# pcb_univ_3-1-0-x-rev2.net
KiCad netlist of a schematic drawn in EAGLE
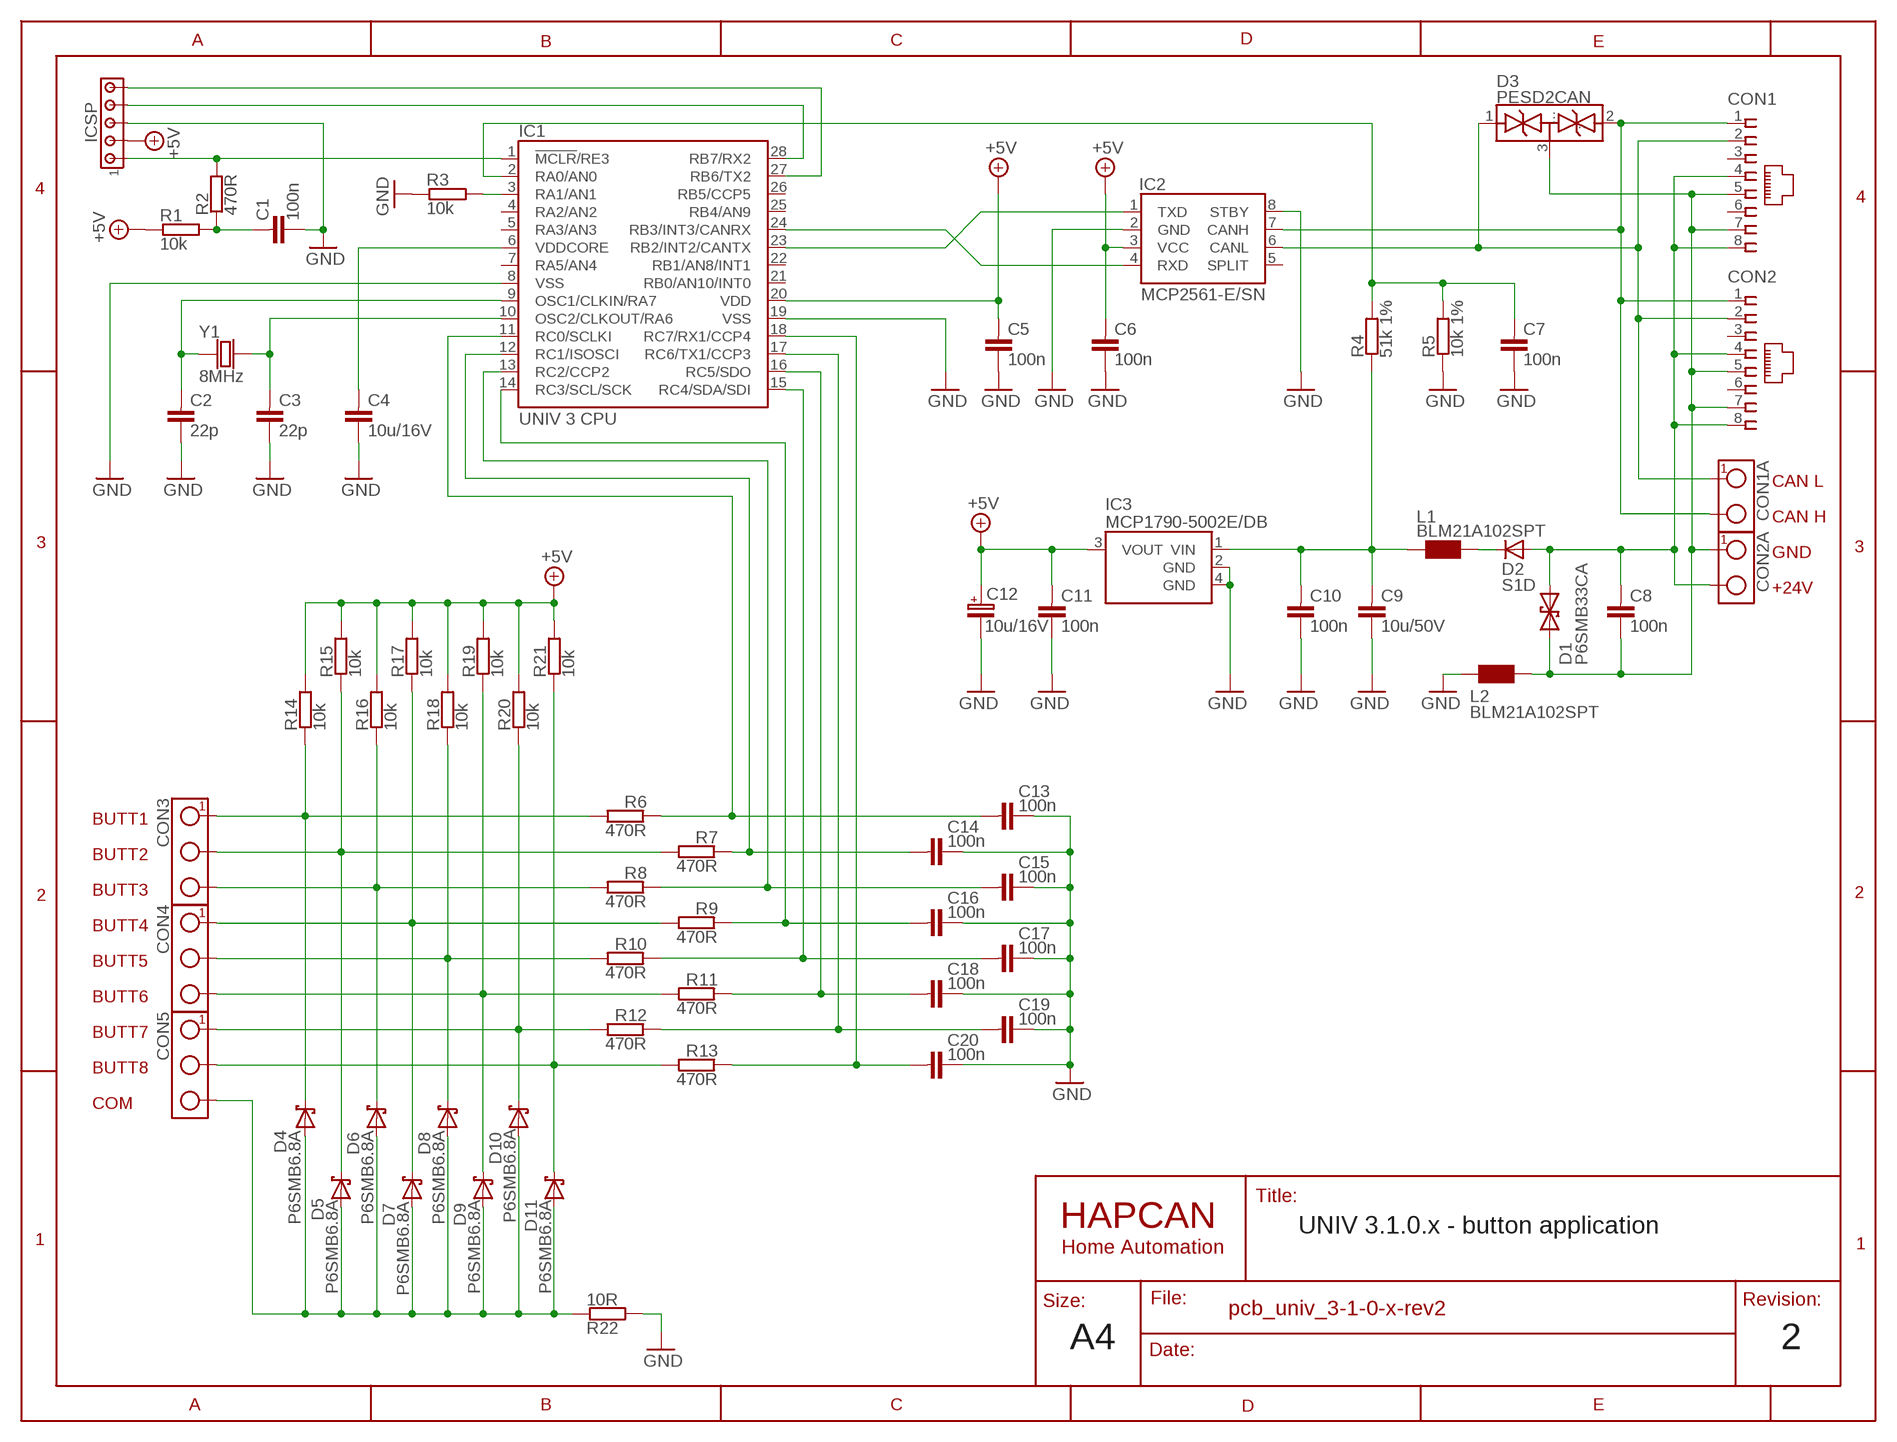
[diagram p0: schematic, sheet 1]

(export (version "E")
  (design (tool "Eeschema 10.0.6"))
  (components
    (comp (ref "C1")
      (value "100n")
      (footprint "eagle-import:0805")
      (libsource (lib "eagle-import") (part "CAPACITOR0805"))
    )
    (comp (ref "C2")
      (value "22p")
      (footprint "eagle-import:0805")
      (libsource (lib "eagle-import") (part "CAPACITOR0805"))
    )
    (comp (ref "C3")
      (value "22p")
      (footprint "eagle-import:0805")
      (libsource (lib "eagle-import") (part "CAPACITOR0805"))
    )
    (comp (ref "C4")
      (value "10u/16V")
      (footprint "eagle-import:0805")
      (libsource (lib "eagle-import") (part "CAPACITOR0805"))
    )
    (comp (ref "C5")
      (value "100n")
      (footprint "eagle-import:0805")
      (libsource (lib "eagle-import") (part "CAPACITOR0805"))
    )
    (comp (ref "C6")
      (value "100n")
      (footprint "eagle-import:0805")
      (libsource (lib "eagle-import") (part "CAPACITOR0805"))
    )
    (comp (ref "C7")
      (value "100n")
      (footprint "eagle-import:0805")
      (libsource (lib "eagle-import") (part "CAPACITOR0805"))
    )
    (comp (ref "C8")
      (value "100n")
      (footprint "eagle-import:0805")
      (libsource (lib "eagle-import") (part "CAPACITOR0805"))
    )
    (comp (ref "C9")
      (value "10u/50V")
      (footprint "eagle-import:1210")
      (libsource (lib "eagle-import") (part "CAPACITOR1210"))
    )
    (comp (ref "C10")
      (value "100n")
      (footprint "eagle-import:0805")
      (libsource (lib "eagle-import") (part "CAPACITOR0805"))
    )
    (comp (ref "C11")
      (value "100n")
      (footprint "eagle-import:0805")
      (libsource (lib "eagle-import") (part "CAPACITOR0805"))
    )
    (comp (ref "C12")
      (value "10u/16V")
      (footprint "eagle-import:SMC_B")
      (libsource (lib "eagle-import") (part "CAPACITOR-POLARIZED-SMC_B"))
    )
    (comp (ref "C13")
      (value "100n")
      (footprint "eagle-import:0805")
      (libsource (lib "eagle-import") (part "CAPACITOR0805"))
    )
    (comp (ref "C14")
      (value "100n")
      (footprint "eagle-import:0805")
      (libsource (lib "eagle-import") (part "CAPACITOR0805"))
    )
    (comp (ref "C15")
      (value "100n")
      (footprint "eagle-import:0805")
      (libsource (lib "eagle-import") (part "CAPACITOR0805"))
    )
    (comp (ref "C16")
      (value "100n")
      (footprint "eagle-import:0805")
      (libsource (lib "eagle-import") (part "CAPACITOR0805"))
    )
    (comp (ref "C17")
      (value "100n")
      (footprint "eagle-import:0805")
      (libsource (lib "eagle-import") (part "CAPACITOR0805"))
    )
    (comp (ref "C18")
      (value "100n")
      (footprint "eagle-import:0805")
      (libsource (lib "eagle-import") (part "CAPACITOR0805"))
    )
    (comp (ref "C19")
      (value "100n")
      (footprint "eagle-import:0805")
      (libsource (lib "eagle-import") (part "CAPACITOR0805"))
    )
    (comp (ref "C20")
      (value "100n")
      (footprint "eagle-import:0805")
      (libsource (lib "eagle-import") (part "CAPACITOR0805"))
    )
    (comp (ref "CON1")
      (value "RJ45-SOCKET")
      (footprint "eagle-import:RJ45-PCB-SOCKET")
      (libsource (lib "eagle-import") (part "RJ45-SOCKET"))
    )
    (comp (ref "CON1A")
      (value "TERMINAL-2")
      (footprint "eagle-import:ARK2-5X10,5MM")
      (libsource (lib "eagle-import") (part "TERMINAL-2-5X10,5MM"))
    )
    (comp (ref "CON2")
      (value "RJ45-SOCKET")
      (footprint "eagle-import:RJ45-PCB-SOCKET")
      (libsource (lib "eagle-import") (part "RJ45-SOCKET"))
    )
    (comp (ref "CON2A")
      (value "TERMINAL-2")
      (footprint "eagle-import:ARK2-5X10,5MM")
      (libsource (lib "eagle-import") (part "TERMINAL-2-5X10,5MM"))
    )
    (comp (ref "CON3")
      (value "TERMINAL-3")
      (footprint "eagle-import:ARK3-5X10.5MM")
      (libsource (lib "eagle-import") (part "TERMINAL-3-5X10.5MM"))
    )
    (comp (ref "CON4")
      (value "TERMINAL-3")
      (footprint "eagle-import:ARK3-5X10.5MM")
      (libsource (lib "eagle-import") (part "TERMINAL-3-5X10.5MM"))
    )
    (comp (ref "CON5")
      (value "TERMINAL-3")
      (footprint "eagle-import:ARK3-5X10.5MM")
      (libsource (lib "eagle-import") (part "TERMINAL-3-5X10.5MM"))
    )
    (comp (ref "D1")
      (value "P6SMB33CA")
      (footprint "eagle-import:DO-214_TRANSIL2")
      (libsource (lib "eagle-import") (part "DIODE_TRANSIL2"))
    )
    (comp (ref "D2")
      (value "S1D")
      (footprint "eagle-import:DO-214")
      (libsource (lib "eagle-import") (part "DIODE_DO-214"))
    )
    (comp (ref "D3")
      (value "PESD2CAN")
      (footprint "eagle-import:SOT-23")
      (libsource (lib "eagle-import") (part "PESD2CANSOT-23"))
    )
    (comp (ref "D4")
      (value "P6SMB6.8A")
      (footprint "eagle-import:DO-214")
      (libsource (lib "eagle-import") (part "DIODE_TRANSIL1_DO214"))
    )
    (comp (ref "D5")
      (value "P6SMB6.8A")
      (footprint "eagle-import:DO-214")
      (libsource (lib "eagle-import") (part "DIODE_TRANSIL1_DO214"))
    )
    (comp (ref "D6")
      (value "P6SMB6.8A")
      (footprint "eagle-import:DO-214")
      (libsource (lib "eagle-import") (part "DIODE_TRANSIL1_DO214"))
    )
    (comp (ref "D7")
      (value "P6SMB6.8A")
      (footprint "eagle-import:DO-214")
      (libsource (lib "eagle-import") (part "DIODE_TRANSIL1_DO214"))
    )
    (comp (ref "D8")
      (value "P6SMB6.8A")
      (footprint "eagle-import:DO-214")
      (libsource (lib "eagle-import") (part "DIODE_TRANSIL1_DO214"))
    )
    (comp (ref "D9")
      (value "P6SMB6.8A")
      (footprint "eagle-import:DO-214")
      (libsource (lib "eagle-import") (part "DIODE_TRANSIL1_DO214"))
    )
    (comp (ref "D10")
      (value "P6SMB6.8A")
      (footprint "eagle-import:DO-214")
      (libsource (lib "eagle-import") (part "DIODE_TRANSIL1_DO214"))
    )
    (comp (ref "D11")
      (value "P6SMB6.8A")
      (footprint "eagle-import:DO-214")
      (libsource (lib "eagle-import") (part "DIODE_TRANSIL1_DO214"))
    )
    (comp (ref "IC1")
      (value "UNIV 3 CPU")
      (footprint "eagle-import:UNIV3CPU")
      (libsource (lib "eagle-import") (part "UNIV3CPU-I/SO"))
    )
    (comp (ref "IC2")
      (value "MCP2561-E/SN")
      (footprint "eagle-import:SO-08")
      (libsource (lib "eagle-import") (part "MCP2561-E/SN"))
    )
    (comp (ref "IC3")
      (value "MCP1790-5002E/DB")
      (footprint "eagle-import:SOT-223")
      (libsource (lib "eagle-import") (part "MCP1790"))
    )
    (comp (ref "ICSP")
      (value "HEADER5")
      (footprint "eagle-import:SIP-5")
      (libsource (lib "eagle-import") (part "HEADER5"))
    )
    (comp (ref "L1")
      (value "BLM21A102SPT")
      (footprint "eagle-import:0805")
      (libsource (lib "eagle-import") (part "CHOKE0805"))
    )
    (comp (ref "L2")
      (value "BLM21A102SPT")
      (footprint "eagle-import:0805")
      (libsource (lib "eagle-import") (part "CHOKE0805"))
    )
    (comp (ref "R1")
      (value "10k")
      (footprint "eagle-import:0805")
      (libsource (lib "eagle-import") (part "RESISTOR0805"))
    )
    (comp (ref "R2")
      (value "470R")
      (footprint "eagle-import:0805")
      (libsource (lib "eagle-import") (part "RESISTOR0805"))
    )
    (comp (ref "R3")
      (value "10k")
      (footprint "eagle-import:0805")
      (libsource (lib "eagle-import") (part "RESISTOR0805"))
    )
    (comp (ref "R4")
      (value "51k 1%")
      (footprint "eagle-import:0805")
      (libsource (lib "eagle-import") (part "RESISTOR0805"))
    )
    (comp (ref "R5")
      (value "10k 1%")
      (footprint "eagle-import:0805")
      (libsource (lib "eagle-import") (part "RESISTOR0805"))
    )
    (comp (ref "R6")
      (value "470R")
      (footprint "eagle-import:0805")
      (libsource (lib "eagle-import") (part "RESISTOR0805"))
    )
    (comp (ref "R7")
      (value "470R")
      (footprint "eagle-import:0805")
      (libsource (lib "eagle-import") (part "RESISTOR0805"))
    )
    (comp (ref "R8")
      (value "470R")
      (footprint "eagle-import:0805")
      (libsource (lib "eagle-import") (part "RESISTOR0805"))
    )
    (comp (ref "R9")
      (value "470R")
      (footprint "eagle-import:0805")
      (libsource (lib "eagle-import") (part "RESISTOR0805"))
    )
    (comp (ref "R10")
      (value "470R")
      (footprint "eagle-import:0805")
      (libsource (lib "eagle-import") (part "RESISTOR0805"))
    )
    (comp (ref "R11")
      (value "470R")
      (footprint "eagle-import:0805")
      (libsource (lib "eagle-import") (part "RESISTOR0805"))
    )
    (comp (ref "R12")
      (value "470R")
      (footprint "eagle-import:0805")
      (libsource (lib "eagle-import") (part "RESISTOR0805"))
    )
    (comp (ref "R13")
      (value "470R")
      (footprint "eagle-import:0805")
      (libsource (lib "eagle-import") (part "RESISTOR0805"))
    )
    (comp (ref "R14")
      (value "10k")
      (footprint "eagle-import:0805")
      (libsource (lib "eagle-import") (part "RESISTOR0805"))
    )
    (comp (ref "R15")
      (value "10k")
      (footprint "eagle-import:0805")
      (libsource (lib "eagle-import") (part "RESISTOR0805"))
    )
    (comp (ref "R16")
      (value "10k")
      (footprint "eagle-import:0805")
      (libsource (lib "eagle-import") (part "RESISTOR0805"))
    )
    (comp (ref "R17")
      (value "10k")
      (footprint "eagle-import:0805")
      (libsource (lib "eagle-import") (part "RESISTOR0805"))
    )
    (comp (ref "R18")
      (value "10k")
      (footprint "eagle-import:0805")
      (libsource (lib "eagle-import") (part "RESISTOR0805"))
    )
    (comp (ref "R19")
      (value "10k")
      (footprint "eagle-import:0805")
      (libsource (lib "eagle-import") (part "RESISTOR0805"))
    )
    (comp (ref "R20")
      (value "10k")
      (footprint "eagle-import:0805")
      (libsource (lib "eagle-import") (part "RESISTOR0805"))
    )
    (comp (ref "R21")
      (value "10k")
      (footprint "eagle-import:0805")
      (libsource (lib "eagle-import") (part "RESISTOR0805"))
    )
    (comp (ref "R22")
      (value "10R")
      (footprint "eagle-import:0805")
      (libsource (lib "eagle-import") (part "RESISTOR0805"))
    )
    (comp (ref "Y1")
      (value "8MHz")
      (footprint "eagle-import:CRYSTAL-HC49V")
      (libsource (lib "eagle-import") (part "CRYSTAL-HC49V"))
    )
  )
  (nets
    (net (code "1") (name "+5V") (class "Default")
      (node (ref "C11") (pin "1") (pinfunction "1_1") (pintype "passive"))
      (node (ref "C12") (pin "+") (pinfunction "1_+") (pintype "passive"))
      (node (ref "C5") (pin "1") (pinfunction "1_1") (pintype "passive"))
      (node (ref "C6") (pin "1") (pinfunction "1_1") (pintype "passive"))
      (node (ref "IC1") (pin "20") (pinfunction "VDD_20") (pintype "bidirectional"))
      (node (ref "IC2") (pin "3") (pinfunction "VCC_3") (pintype "bidirectional"))
      (node (ref "IC3") (pin "3") (pinfunction "VOUT_3") (pintype "bidirectional"))
      (node (ref "ICSP") (pin "2") (pinfunction "2_2") (pintype "passive"))
      (node (ref "R1") (pin "1") (pinfunction "1_1") (pintype "passive"))
      (node (ref "R14") (pin "2") (pinfunction "2_2") (pintype "passive"))
      (node (ref "R15") (pin "2") (pinfunction "2_2") (pintype "passive"))
      (node (ref "R16") (pin "2") (pinfunction "2_2") (pintype "passive"))
      (node (ref "R17") (pin "2") (pinfunction "2_2") (pintype "passive"))
      (node (ref "R18") (pin "2") (pinfunction "2_2") (pintype "passive"))
      (node (ref "R19") (pin "2") (pinfunction "2_2") (pintype "passive"))
      (node (ref "R20") (pin "2") (pinfunction "2_2") (pintype "passive"))
      (node (ref "R21") (pin "2") (pinfunction "2_2") (pintype "passive"))
    )
    (net (code "2") (name "GND") (class "Default")
      (node (ref "C1") (pin "2") (pinfunction "2_2") (pintype "passive"))
      (node (ref "C10") (pin "2") (pinfunction "2_2") (pintype "passive"))
      (node (ref "C11") (pin "2") (pinfunction "2_2") (pintype "passive"))
      (node (ref "C12") (pin "-") (pinfunction "2_-") (pintype "passive"))
      (node (ref "C13") (pin "2") (pinfunction "2_2") (pintype "passive"))
      (node (ref "C14") (pin "2") (pinfunction "2_2") (pintype "passive"))
      (node (ref "C15") (pin "2") (pinfunction "2_2") (pintype "passive"))
      (node (ref "C16") (pin "2") (pinfunction "2_2") (pintype "passive"))
      (node (ref "C17") (pin "2") (pinfunction "2_2") (pintype "passive"))
      (node (ref "C18") (pin "2") (pinfunction "2_2") (pintype "passive"))
      (node (ref "C19") (pin "2") (pinfunction "2_2") (pintype "passive"))
      (node (ref "C2") (pin "2") (pinfunction "2_2") (pintype "passive"))
      (node (ref "C20") (pin "2") (pinfunction "2_2") (pintype "passive"))
      (node (ref "C3") (pin "2") (pinfunction "2_2") (pintype "passive"))
      (node (ref "C4") (pin "2") (pinfunction "2_2") (pintype "passive"))
      (node (ref "C5") (pin "2") (pinfunction "2_2") (pintype "passive"))
      (node (ref "C6") (pin "2") (pinfunction "2_2") (pintype "passive"))
      (node (ref "C7") (pin "2") (pinfunction "2_2") (pintype "passive"))
      (node (ref "C9") (pin "2") (pinfunction "2_2") (pintype "passive"))
      (node (ref "IC1") (pin "19") (pinfunction "VSS_19") (pintype "bidirectional"))
      (node (ref "IC1") (pin "8") (pinfunction "VSS_8") (pintype "bidirectional"))
      (node (ref "IC2") (pin "2") (pinfunction "GND_2") (pintype "bidirectional"))
      (node (ref "IC2") (pin "8") (pinfunction "STBY_8") (pintype "bidirectional"))
      (node (ref "IC3") (pin "2") (pinfunction "GND_2") (pintype "bidirectional"))
      (node (ref "IC3") (pin "4") (pinfunction "GND_4") (pintype "bidirectional"))
      (node (ref "ICSP") (pin "3") (pinfunction "3_3") (pintype "passive"))
      (node (ref "L2") (pin "1") (pinfunction "1_1") (pintype "passive"))
      (node (ref "R22") (pin "2") (pinfunction "2_2") (pintype "passive"))
      (node (ref "R3") (pin "1") (pinfunction "1_1") (pintype "passive"))
      (node (ref "R5") (pin "1") (pinfunction "1_1") (pintype "passive"))
    )
    (net (code "3") (name "Net-(C1-Pad1)") (class "Default")
      (node (ref "C1") (pin "1") (pinfunction "1_1") (pintype "passive"))
      (node (ref "R1") (pin "2") (pinfunction "2_2") (pintype "passive"))
      (node (ref "R2") (pin "1") (pinfunction "1_1") (pintype "passive"))
    )
    (net (code "4") (name "Net-(CON3-Pad1)") (class "Default")
      (node (ref "CON3") (pin "1") (pinfunction "1_1") (pintype "passive"))
      (node (ref "D4") (pin "C") (pinfunction "C_C") (pintype "passive"))
      (node (ref "R14") (pin "1") (pinfunction "1_1") (pintype "passive"))
      (node (ref "R6") (pin "2") (pinfunction "2_2") (pintype "passive"))
    )
    (net (code "5") (name "Net-(CON3-Pad2)") (class "Default")
      (node (ref "CON3") (pin "2") (pinfunction "2_2") (pintype "passive"))
      (node (ref "D5") (pin "C") (pinfunction "C_C") (pintype "passive"))
      (node (ref "R15") (pin "1") (pinfunction "1_1") (pintype "passive"))
      (node (ref "R7") (pin "2") (pinfunction "2_2") (pintype "passive"))
    )
    (net (code "6") (name "Net-(CON3-Pad3)") (class "Default")
      (node (ref "CON3") (pin "3") (pinfunction "3_3") (pintype "passive"))
      (node (ref "D6") (pin "C") (pinfunction "C_C") (pintype "passive"))
      (node (ref "R16") (pin "1") (pinfunction "1_1") (pintype "passive"))
      (node (ref "R8") (pin "2") (pinfunction "2_2") (pintype "passive"))
    )
    (net (code "7") (name "Net-(CON4-Pad1)") (class "Default")
      (node (ref "CON4") (pin "1") (pinfunction "1_1") (pintype "passive"))
      (node (ref "D7") (pin "C") (pinfunction "C_C") (pintype "passive"))
      (node (ref "R17") (pin "1") (pinfunction "1_1") (pintype "passive"))
      (node (ref "R9") (pin "2") (pinfunction "2_2") (pintype "passive"))
    )
    (net (code "8") (name "Net-(CON4-Pad2)") (class "Default")
      (node (ref "CON4") (pin "2") (pinfunction "2_2") (pintype "passive"))
      (node (ref "D8") (pin "C") (pinfunction "C_C") (pintype "passive"))
      (node (ref "R10") (pin "2") (pinfunction "2_2") (pintype "passive"))
      (node (ref "R18") (pin "1") (pinfunction "1_1") (pintype "passive"))
    )
    (net (code "9") (name "Net-(CON4-Pad3)") (class "Default")
      (node (ref "CON4") (pin "3") (pinfunction "3_3") (pintype "passive"))
      (node (ref "D9") (pin "C") (pinfunction "C_C") (pintype "passive"))
      (node (ref "R11") (pin "2") (pinfunction "2_2") (pintype "passive"))
      (node (ref "R19") (pin "1") (pinfunction "1_1") (pintype "passive"))
    )
    (net (code "10") (name "Net-(CON5-Pad1)") (class "Default")
      (node (ref "CON5") (pin "1") (pinfunction "1_1") (pintype "passive"))
      (node (ref "D10") (pin "C") (pinfunction "C_C") (pintype "passive"))
      (node (ref "R12") (pin "2") (pinfunction "2_2") (pintype "passive"))
      (node (ref "R20") (pin "1") (pinfunction "1_1") (pintype "passive"))
    )
    (net (code "11") (name "Net-(CON5-Pad2)") (class "Default")
      (node (ref "CON5") (pin "2") (pinfunction "2_2") (pintype "passive"))
      (node (ref "D11") (pin "C") (pinfunction "C_C") (pintype "passive"))
      (node (ref "R13") (pin "2") (pinfunction "2_2") (pintype "passive"))
      (node (ref "R21") (pin "1") (pinfunction "1_1") (pintype "passive"))
    )
    (net (code "12") (name "Net-(CON5-Pad3)") (class "Default")
      (node (ref "CON5") (pin "3") (pinfunction "3_3") (pintype "passive"))
      (node (ref "D10") (pin "A") (pinfunction "A_A") (pintype "passive"))
      (node (ref "D11") (pin "A") (pinfunction "A_A") (pintype "passive"))
      (node (ref "D4") (pin "A") (pinfunction "A_A") (pintype "passive"))
      (node (ref "D5") (pin "A") (pinfunction "A_A") (pintype "passive"))
      (node (ref "D6") (pin "A") (pinfunction "A_A") (pintype "passive"))
      (node (ref "D7") (pin "A") (pinfunction "A_A") (pintype "passive"))
      (node (ref "D8") (pin "A") (pinfunction "A_A") (pintype "passive"))
      (node (ref "D9") (pin "A") (pinfunction "A_A") (pintype "passive"))
      (node (ref "R22") (pin "1") (pinfunction "1_1") (pintype "passive"))
    )
    (net (code "13") (name "Net-(D1-1)") (class "Default")
      (node (ref "C8") (pin "1") (pinfunction "1_1") (pintype "passive"))
      (node (ref "CON1") (pin "4") (pinfunction "4_4") (pintype "passive"))
      (node (ref "CON1") (pin "8") (pinfunction "8_8") (pintype "passive"))
      (node (ref "CON2") (pin "4") (pinfunction "4_4") (pintype "passive"))
      (node (ref "CON2") (pin "8") (pinfunction "8_8") (pintype "passive"))
      (node (ref "CON2A") (pin "2") (pinfunction "2_2") (pintype "passive"))
      (node (ref "D1") (pin "A") (pinfunction "1_A") (pintype "passive"))
      (node (ref "D2") (pin "A") (pinfunction "A_A") (pintype "passive"))
    )
    (net (code "14") (name "Net-(D1-2)") (class "Default")
      (node (ref "C8") (pin "2") (pinfunction "2_2") (pintype "passive"))
      (node (ref "CON1") (pin "5") (pinfunction "5_5") (pintype "passive"))
      (node (ref "CON1") (pin "7") (pinfunction "7_7") (pintype "passive"))
      (node (ref "CON2") (pin "5") (pinfunction "5_5") (pintype "passive"))
      (node (ref "CON2") (pin "7") (pinfunction "7_7") (pintype "passive"))
      (node (ref "CON2A") (pin "1") (pinfunction "1_1") (pintype "passive"))
      (node (ref "D1") (pin "C") (pinfunction "2_C") (pintype "passive"))
      (node (ref "D3") (pin "3") (pinfunction "..._3") (pintype "bidirectional"))
      (node (ref "L2") (pin "2") (pinfunction "2_2") (pintype "passive"))
    )
    (net (code "15") (name "Net-(D2-PadC)") (class "Default")
      (node (ref "D2") (pin "C") (pinfunction "C_C") (pintype "passive"))
      (node (ref "L1") (pin "2") (pinfunction "2_2") (pintype "passive"))
    )
    (net (code "16") (name "Net-(D3-.)") (class "Default")
      (node (ref "CON1") (pin "2") (pinfunction "2_2") (pintype "passive"))
      (node (ref "CON1A") (pin "1") (pinfunction "1_1") (pintype "passive"))
      (node (ref "CON2") (pin "2") (pinfunction "2_2") (pintype "passive"))
      (node (ref "D3") (pin "1") (pinfunction "._1") (pintype "bidirectional"))
      (node (ref "IC2") (pin "6") (pinfunction "CANL_6") (pintype "bidirectional"))
    )
    (net (code "17") (name "Net-(D3-..)") (class "Default")
      (node (ref "CON1") (pin "1") (pinfunction "1_1") (pintype "passive"))
      (node (ref "CON1A") (pin "2") (pinfunction "2_2") (pintype "passive"))
      (node (ref "CON2") (pin "1") (pinfunction "1_1") (pintype "passive"))
      (node (ref "D3") (pin "2") (pinfunction ".._2") (pintype "bidirectional"))
      (node (ref "IC2") (pin "7") (pinfunction "CANH_7") (pintype "bidirectional"))
    )
    (net (code "18") (name "Net-(IC1-OSC1{slash}CLKIN{slash}RA7)") (class "Default")
      (node (ref "C2") (pin "1") (pinfunction "1_1") (pintype "passive"))
      (node (ref "IC1") (pin "9") (pinfunction "OSC1/CLKIN/RA7_9") (pintype "bidirectional"))
      (node (ref "Y1") (pin "1") (pinfunction "1_1") (pintype "passive"))
    )
    (net (code "19") (name "Net-(IC1-OSC2{slash}CLKOUT{slash}RA6)") (class "Default")
      (node (ref "C3") (pin "1") (pinfunction "1_1") (pintype "passive"))
      (node (ref "IC1") (pin "10") (pinfunction "OSC2/CLKOUT/RA6_10") (pintype "bidirectional"))
      (node (ref "Y1") (pin "2") (pinfunction "2_2") (pintype "passive"))
    )
    (net (code "20") (name "Net-(IC1-RA0{slash}AN0)") (class "Default")
      (node (ref "C7") (pin "1") (pinfunction "1_1") (pintype "passive"))
      (node (ref "IC1") (pin "2") (pinfunction "RA0/AN0_2") (pintype "bidirectional"))
      (node (ref "R4") (pin "2") (pinfunction "2_2") (pintype "passive"))
      (node (ref "R5") (pin "2") (pinfunction "2_2") (pintype "passive"))
    )
    (net (code "21") (name "Net-(IC1-RA1{slash}AN1)") (class "Default")
      (node (ref "IC1") (pin "3") (pinfunction "RA1/AN1_3") (pintype "bidirectional"))
      (node (ref "R3") (pin "2") (pinfunction "2_2") (pintype "passive"))
    )
    (net (code "22") (name "Net-(IC1-RB2{slash}INT2{slash}CANTX)") (class "Default")
      (node (ref "IC1") (pin "23") (pinfunction "RB2/INT2/CANTX_23") (pintype "bidirectional"))
      (node (ref "IC2") (pin "1") (pinfunction "TXD_1") (pintype "bidirectional"))
    )
    (net (code "23") (name "Net-(IC1-RB3{slash}INT3{slash}CANRX)") (class "Default")
      (node (ref "IC1") (pin "24") (pinfunction "RB3/INT3/CANRX_24") (pintype "bidirectional"))
      (node (ref "IC2") (pin "4") (pinfunction "RXD_4") (pintype "bidirectional"))
    )
    (net (code "24") (name "Net-(IC1-RB6{slash}TX2)") (class "Default")
      (node (ref "IC1") (pin "27") (pinfunction "RB6/TX2_27") (pintype "bidirectional"))
      (node (ref "ICSP") (pin "5") (pinfunction "5_5") (pintype "passive"))
    )
    (net (code "25") (name "Net-(IC1-RB7{slash}RX2)") (class "Default")
      (node (ref "IC1") (pin "28") (pinfunction "RB7/RX2_28") (pintype "bidirectional"))
      (node (ref "ICSP") (pin "4") (pinfunction "4_4") (pintype "passive"))
    )
    (net (code "26") (name "Net-(IC1-RC0{slash}SCLKI)") (class "Default")
      (node (ref "C13") (pin "1") (pinfunction "1_1") (pintype "passive"))
      (node (ref "IC1") (pin "11") (pinfunction "RC0/SCLKI_11") (pintype "bidirectional"))
      (node (ref "R6") (pin "1") (pinfunction "1_1") (pintype "passive"))
    )
    (net (code "27") (name "Net-(IC1-RC1{slash}ISOSCI)") (class "Default")
      (node (ref "C14") (pin "1") (pinfunction "1_1") (pintype "passive"))
      (node (ref "IC1") (pin "12") (pinfunction "RC1/ISOSCI_12") (pintype "bidirectional"))
      (node (ref "R7") (pin "1") (pinfunction "1_1") (pintype "passive"))
    )
    (net (code "28") (name "Net-(IC1-RC2{slash}CCP2)") (class "Default")
      (node (ref "C15") (pin "1") (pinfunction "1_1") (pintype "passive"))
      (node (ref "IC1") (pin "13") (pinfunction "RC2/CCP2_13") (pintype "bidirectional"))
      (node (ref "R8") (pin "1") (pinfunction "1_1") (pintype "passive"))
    )
    (net (code "29") (name "Net-(IC1-RC3{slash}SCL{slash}SCK)") (class "Default")
      (node (ref "C16") (pin "1") (pinfunction "1_1") (pintype "passive"))
      (node (ref "IC1") (pin "14") (pinfunction "RC3/SCL/SCK_14") (pintype "bidirectional"))
      (node (ref "R9") (pin "1") (pinfunction "1_1") (pintype "passive"))
    )
    (net (code "30") (name "Net-(IC1-RC4{slash}SDA{slash}SDI)") (class "Default")
      (node (ref "C17") (pin "1") (pinfunction "1_1") (pintype "passive"))
      (node (ref "IC1") (pin "15") (pinfunction "RC4/SDA/SDI_15") (pintype "bidirectional"))
      (node (ref "R10") (pin "1") (pinfunction "1_1") (pintype "passive"))
    )
    (net (code "31") (name "Net-(IC1-RC5{slash}SDO)") (class "Default")
      (node (ref "C18") (pin "1") (pinfunction "1_1") (pintype "passive"))
      (node (ref "IC1") (pin "16") (pinfunction "RC5/SDO_16") (pintype "bidirectional"))
      (node (ref "R11") (pin "1") (pinfunction "1_1") (pintype "passive"))
    )
    (net (code "32") (name "Net-(IC1-RC6{slash}TX1{slash}CCP3)") (class "Default")
      (node (ref "C19") (pin "1") (pinfunction "1_1") (pintype "passive"))
      (node (ref "IC1") (pin "17") (pinfunction "RC6/TX1/CCP3_17") (pintype "bidirectional"))
      (node (ref "R12") (pin "1") (pinfunction "1_1") (pintype "passive"))
    )
    (net (code "33") (name "Net-(IC1-RC7{slash}RX1{slash}CCP4)") (class "Default")
      (node (ref "C20") (pin "1") (pinfunction "1_1") (pintype "passive"))
      (node (ref "IC1") (pin "18") (pinfunction "RC7/RX1/CCP4_18") (pintype "bidirectional"))
      (node (ref "R13") (pin "1") (pinfunction "1_1") (pintype "passive"))
    )
    (net (code "34") (name "Net-(IC1-VDDCORE)") (class "Default")
      (node (ref "C4") (pin "1") (pinfunction "1_1") (pintype "passive"))
      (node (ref "IC1") (pin "6") (pinfunction "VDDCORE_6") (pintype "bidirectional"))
    )
    (net (code "35") (name "Net-(IC1-~{MCLR}{slash}RE3)") (class "Default")
      (node (ref "IC1") (pin "1") (pinfunction "~{MCLR}/RE3_1") (pintype "bidirectional"))
      (node (ref "ICSP") (pin "1") (pinfunction "1_1") (pintype "passive"))
      (node (ref "R2") (pin "2") (pinfunction "2_2") (pintype "passive"))
    )
    (net (code "36") (name "Net-(IC3-VIN)") (class "Default")
      (node (ref "C10") (pin "1") (pinfunction "1_1") (pintype "passive"))
      (node (ref "C9") (pin "1") (pinfunction "1_1") (pintype "passive"))
      (node (ref "IC3") (pin "1") (pinfunction "VIN_1") (pintype "bidirectional"))
      (node (ref "L1") (pin "1") (pinfunction "1_1") (pintype "passive"))
      (node (ref "R4") (pin "1") (pinfunction "1_1") (pintype "passive"))
    )
    (net (code "37") (name "unconnected-(CON1-Pad3)") (class "Default")
      (node (ref "CON1") (pin "3") (pinfunction "3_3") (pintype "passive"))
    )
    (net (code "38") (name "unconnected-(CON1-Pad6)") (class "Default")
      (node (ref "CON1") (pin "6") (pinfunction "6_6") (pintype "passive"))
    )
    (net (code "39") (name "unconnected-(CON2-Pad3)") (class "Default")
      (node (ref "CON2") (pin "3") (pinfunction "3_3") (pintype "passive"))
    )
    (net (code "40") (name "unconnected-(CON2-Pad6)") (class "Default")
      (node (ref "CON2") (pin "6") (pinfunction "6_6") (pintype "passive"))
    )
    (net (code "41") (name "unconnected-(IC1-RA2{slash}AN2-Pad4)") (class "Default")
      (node (ref "IC1") (pin "4") (pinfunction "RA2/AN2_4") (pintype "bidirectional"))
    )
    (net (code "42") (name "unconnected-(IC1-RA3{slash}AN3-Pad5)") (class "Default")
      (node (ref "IC1") (pin "5") (pinfunction "RA3/AN3_5") (pintype "bidirectional"))
    )
    (net (code "43") (name "unconnected-(IC1-RA5{slash}AN4-Pad7)") (class "Default")
      (node (ref "IC1") (pin "7") (pinfunction "RA5/AN4_7") (pintype "bidirectional"))
    )
    (net (code "44") (name "unconnected-(IC1-RB0{slash}AN10{slash}INT0-Pad21)") (class "Default")
      (node (ref "IC1") (pin "21") (pinfunction "RB0/AN10/INT0_21") (pintype "bidirectional"))
    )
    (net (code "45") (name "unconnected-(IC1-RB1{slash}AN8{slash}INT1-Pad22)") (class "Default")
      (node (ref "IC1") (pin "22") (pinfunction "RB1/AN8/INT1_22") (pintype "bidirectional"))
    )
    (net (code "46") (name "unconnected-(IC1-RB4{slash}AN9-Pad25)") (class "Default")
      (node (ref "IC1") (pin "25") (pinfunction "RB4/AN9_25") (pintype "bidirectional"))
    )
    (net (code "47") (name "unconnected-(IC1-RB5{slash}CCP5-Pad26)") (class "Default")
      (node (ref "IC1") (pin "26") (pinfunction "RB5/CCP5_26") (pintype "bidirectional"))
    )
    (net (code "48") (name "unconnected-(IC2-SPLIT-Pad5)") (class "Default")
      (node (ref "IC2") (pin "5") (pinfunction "SPLIT_5") (pintype "bidirectional"))
    )
  )
)
